# PulseSensor.net
KiCad netlist of a schematic drawn in EAGLE
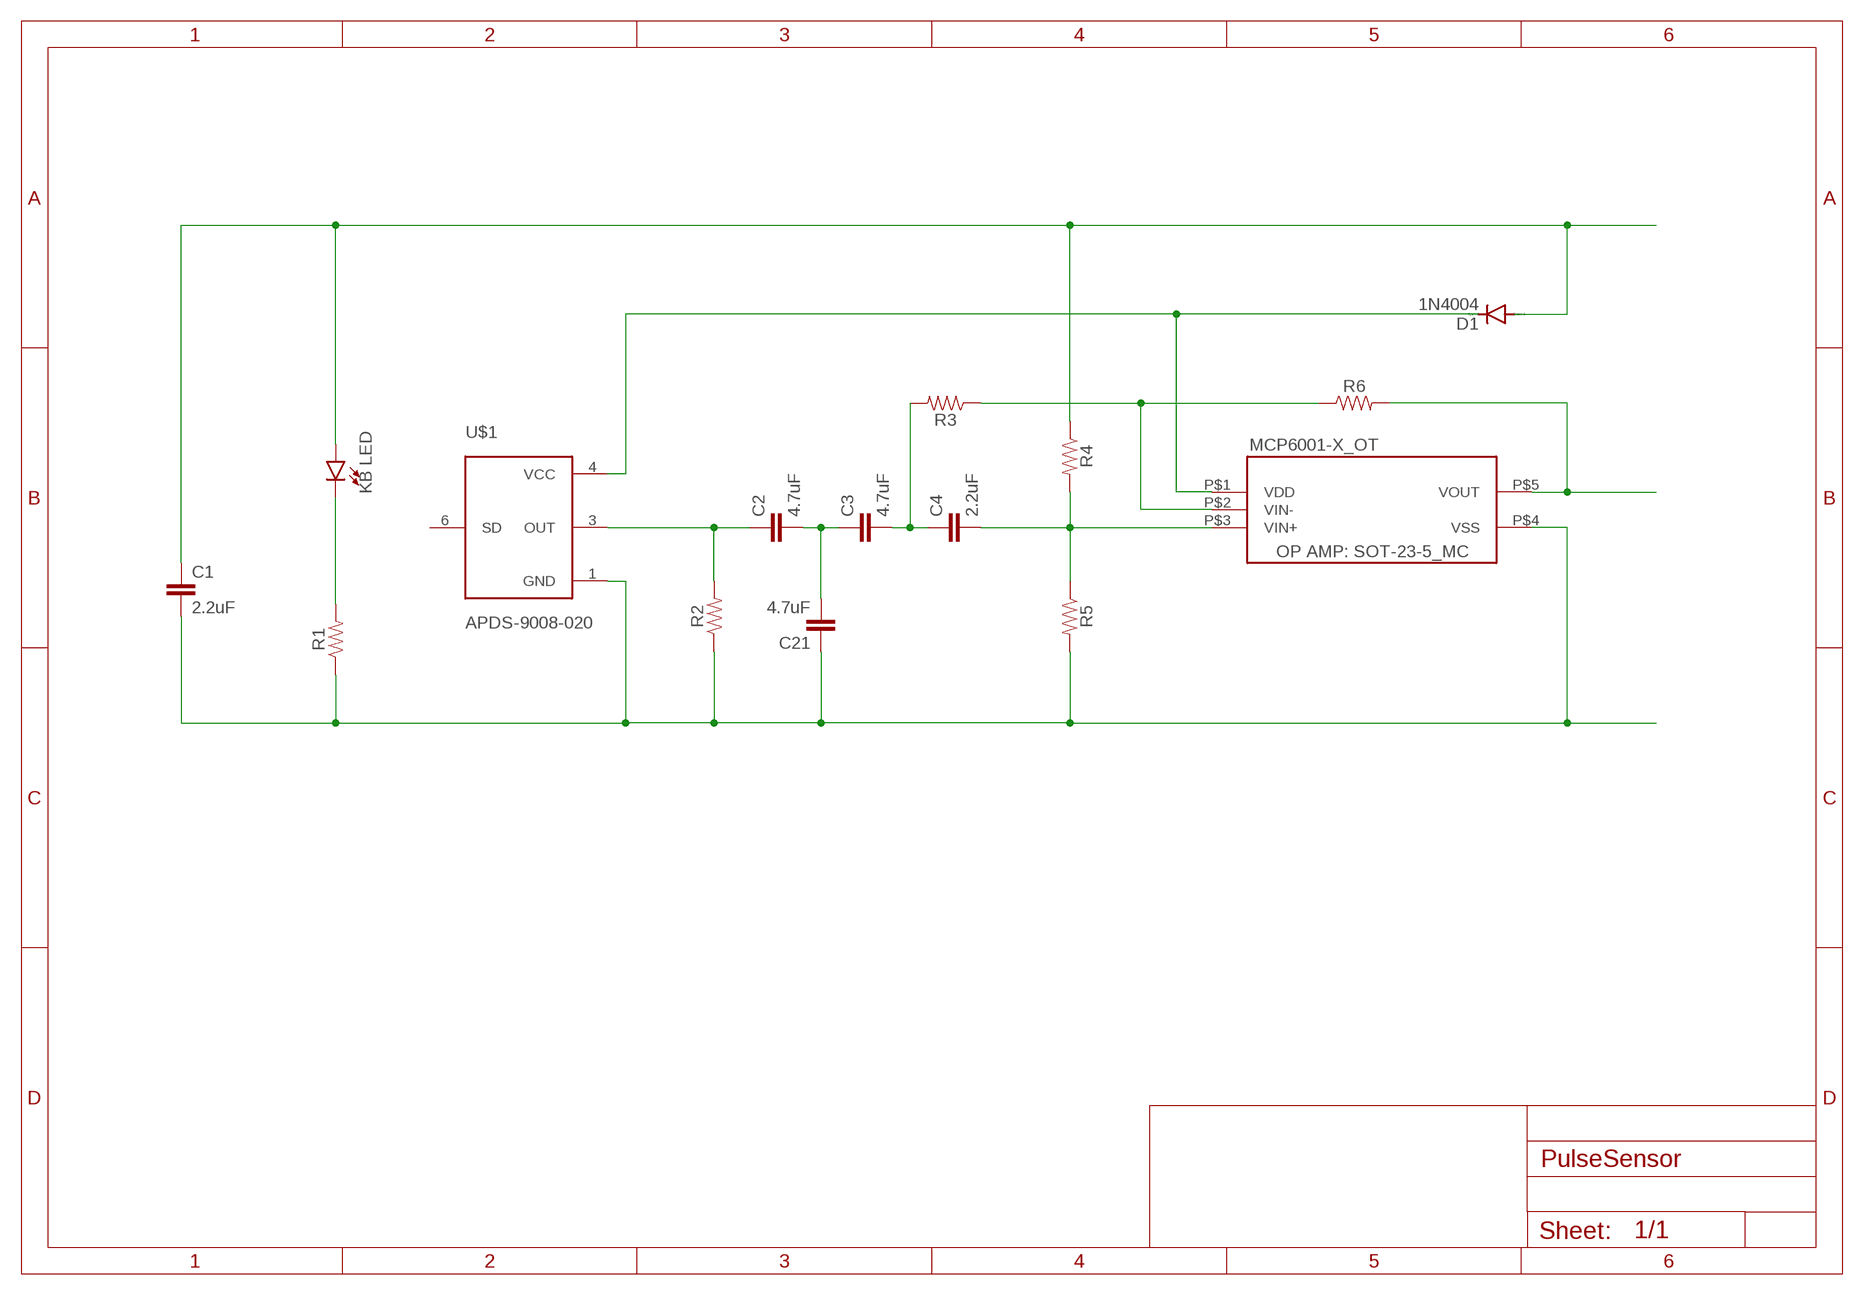
[diagram p0: schematic, sheet 1]

(export (version "E")
  (design (tool "Eeschema 10.0.6"))
  (components
    (comp (ref "C1")
      (value "2.2uF")
      (footprint "eagle-import:0603")
      (libsource (lib "eagle-import") (part "2.2UF-0603-10V-20%"))
    )
    (comp (ref "C2")
      (value "4.7uF")
      (footprint "eagle-import:0603")
      (libsource (lib "eagle-import") (part "4.7UF0603"))
    )
    (comp (ref "C3")
      (value "4.7uF")
      (footprint "eagle-import:0603")
      (libsource (lib "eagle-import") (part "4.7UF0603"))
    )
    (comp (ref "C4")
      (value "2.2uF")
      (footprint "eagle-import:0603")
      (libsource (lib "eagle-import") (part "2.2UF-0603-10V-20%"))
    )
    (comp (ref "C21")
      (value "4.7uF")
      (footprint "eagle-import:0603")
      (libsource (lib "eagle-import") (part "4.7UF0603"))
    )
    (comp (ref "D1")
      (value "1N4004")
      (footprint "eagle-import:DO41-10")
      (libsource (lib "eagle-import") (part "1N4004"))
    )
    (comp (ref "R1")
      (value "RESISTOR0603")
      (footprint "eagle-import:0603")
      (libsource (lib "eagle-import") (part "RESISTOR0603"))
    )
    (comp (ref "R2")
      (value "RESISTOR0603")
      (footprint "eagle-import:0603")
      (libsource (lib "eagle-import") (part "RESISTOR0603"))
    )
    (comp (ref "R3")
      (value "RESISTOR0603")
      (footprint "eagle-import:0603")
      (libsource (lib "eagle-import") (part "RESISTOR0603"))
    )
    (comp (ref "R4")
      (value "RESISTOR0603")
      (footprint "eagle-import:0603")
      (libsource (lib "eagle-import") (part "RESISTOR0603"))
    )
    (comp (ref "R5")
      (value "RESISTOR0603")
      (footprint "eagle-import:0603")
      (libsource (lib "eagle-import") (part "RESISTOR0603"))
    )
    (comp (ref "R6")
      (value "RESISTOR0603")
      (footprint "eagle-import:0603")
      (libsource (lib "eagle-import") (part "RESISTOR0603"))
    )
    (comp (ref "U$1")
      (value "APDS-9008-020")
      (footprint "eagle-import:LCC140P200X240X80-6")
      (fields (field (name "MF") "Broadcom Limited"))
      (libsource (lib "eagle-import") (part "APDS-9008-020"))
    )
    (comp (ref "U$2")
      (value "KB_REVMNT_LED")
      (footprint "eagle-import:REVMNT_LED_FP")
      (libsource (lib "eagle-import") (part "KB_REVMNT_LED"))
    )
    (comp (ref "U$3")
      (value "MCP6001-X_SOT-23-5")
      (footprint "eagle-import:SOT-23-5")
      (libsource (lib "eagle-import") (part "MCP6001-X_SOT-23-5"))
    )
  )
  (nets
    (net (code "1") (name "Net-(C2-Pad2)") (class "Default")
      (node (ref "C2") (pin "2") (pinfunction "2_2") (pintype "passive"))
      (node (ref "C21") (pin "2") (pinfunction "2_2") (pintype "passive"))
      (node (ref "C3") (pin "1") (pinfunction "1_1") (pintype "passive"))
    )
    (net (code "2") (name "Net-(C3-Pad2)") (class "Default")
      (node (ref "C3") (pin "2") (pinfunction "2_2") (pintype "passive"))
      (node (ref "C4") (pin "1") (pinfunction "1_1") (pintype "passive"))
      (node (ref "R3") (pin "2") (pinfunction "2_2") (pintype "passive"))
    )
    (net (code "3") (name "Net-(U$1-GND)") (class "Default")
      (node (ref "C1") (pin "2") (pinfunction "2_2") (pintype "passive"))
      (node (ref "C21") (pin "1") (pinfunction "1_1") (pintype "passive"))
      (node (ref "R1") (pin "1") (pinfunction "1_1") (pintype "passive"))
      (node (ref "R2") (pin "1") (pinfunction "1_1") (pintype "passive"))
      (node (ref "R5") (pin "2") (pinfunction "2_2") (pintype "passive"))
      (node (ref "U$1") (pin "1") (pinfunction "GND_1") (pintype "passive"))
      (node (ref "U$3") (pin "P$4") (pinfunction "VSS_P$4") (pintype "power_in"))
    )
    (net (code "4") (name "Net-(U$1-OUT)") (class "Default")
      (node (ref "C2") (pin "1") (pinfunction "1_1") (pintype "passive"))
      (node (ref "R2") (pin "2") (pinfunction "2_2") (pintype "passive"))
      (node (ref "U$1") (pin "3") (pinfunction "OUT_3") (pintype "output"))
    )
    (net (code "5") (name "Net-(U$1-VCC)") (class "Default")
      (node (ref "D1") (pin "C") (pinfunction "C_C") (pintype "passive"))
      (node (ref "U$1") (pin "4") (pinfunction "VCC_4") (pintype "power_in"))
      (node (ref "U$3") (pin "P$1") (pinfunction "VDD_P$1") (pintype "power_in"))
    )
    (net (code "6") (name "Net-(U$2-A)") (class "Default")
      (node (ref "C1") (pin "1") (pinfunction "1_1") (pintype "passive"))
      (node (ref "D1") (pin "A") (pinfunction "A_A") (pintype "passive"))
      (node (ref "R4") (pin "1") (pinfunction "1_1") (pintype "passive"))
      (node (ref "U$2") (pin "P$1") (pinfunction "A_P$1") (pintype "passive"))
    )
    (net (code "7") (name "Net-(U$2-C)") (class "Default")
      (node (ref "R1") (pin "2") (pinfunction "2_2") (pintype "passive"))
      (node (ref "U$2") (pin "P$2") (pinfunction "C_P$2") (pintype "passive"))
    )
    (net (code "8") (name "Net-(U$3-VIN+)") (class "Default")
      (node (ref "C4") (pin "2") (pinfunction "2_2") (pintype "passive"))
      (node (ref "R4") (pin "2") (pinfunction "2_2") (pintype "passive"))
      (node (ref "R5") (pin "1") (pinfunction "1_1") (pintype "passive"))
      (node (ref "U$3") (pin "P$3") (pinfunction "VIN+_P$3") (pintype "input"))
    )
    (net (code "9") (name "Net-(U$3-VIN-)") (class "Default")
      (node (ref "R3") (pin "1") (pinfunction "1_1") (pintype "passive"))
      (node (ref "R6") (pin "1") (pinfunction "1_1") (pintype "passive"))
      (node (ref "U$3") (pin "P$2") (pinfunction "VIN-_P$2") (pintype "input"))
    )
    (net (code "10") (name "Net-(U$3-VOUT)") (class "Default")
      (node (ref "R6") (pin "2") (pinfunction "2_2") (pintype "passive"))
      (node (ref "U$3") (pin "P$5") (pinfunction "VOUT_P$5") (pintype "output"))
    )
    (net (code "11") (name "unconnected-(U$1-SD-Pad6)") (class "Default")
      (node (ref "U$1") (pin "6") (pinfunction "SD_6") (pintype "input"))
    )
  )
)
